# iDProx.net
KiCad netlist of a schematic drawn in Altium Designer
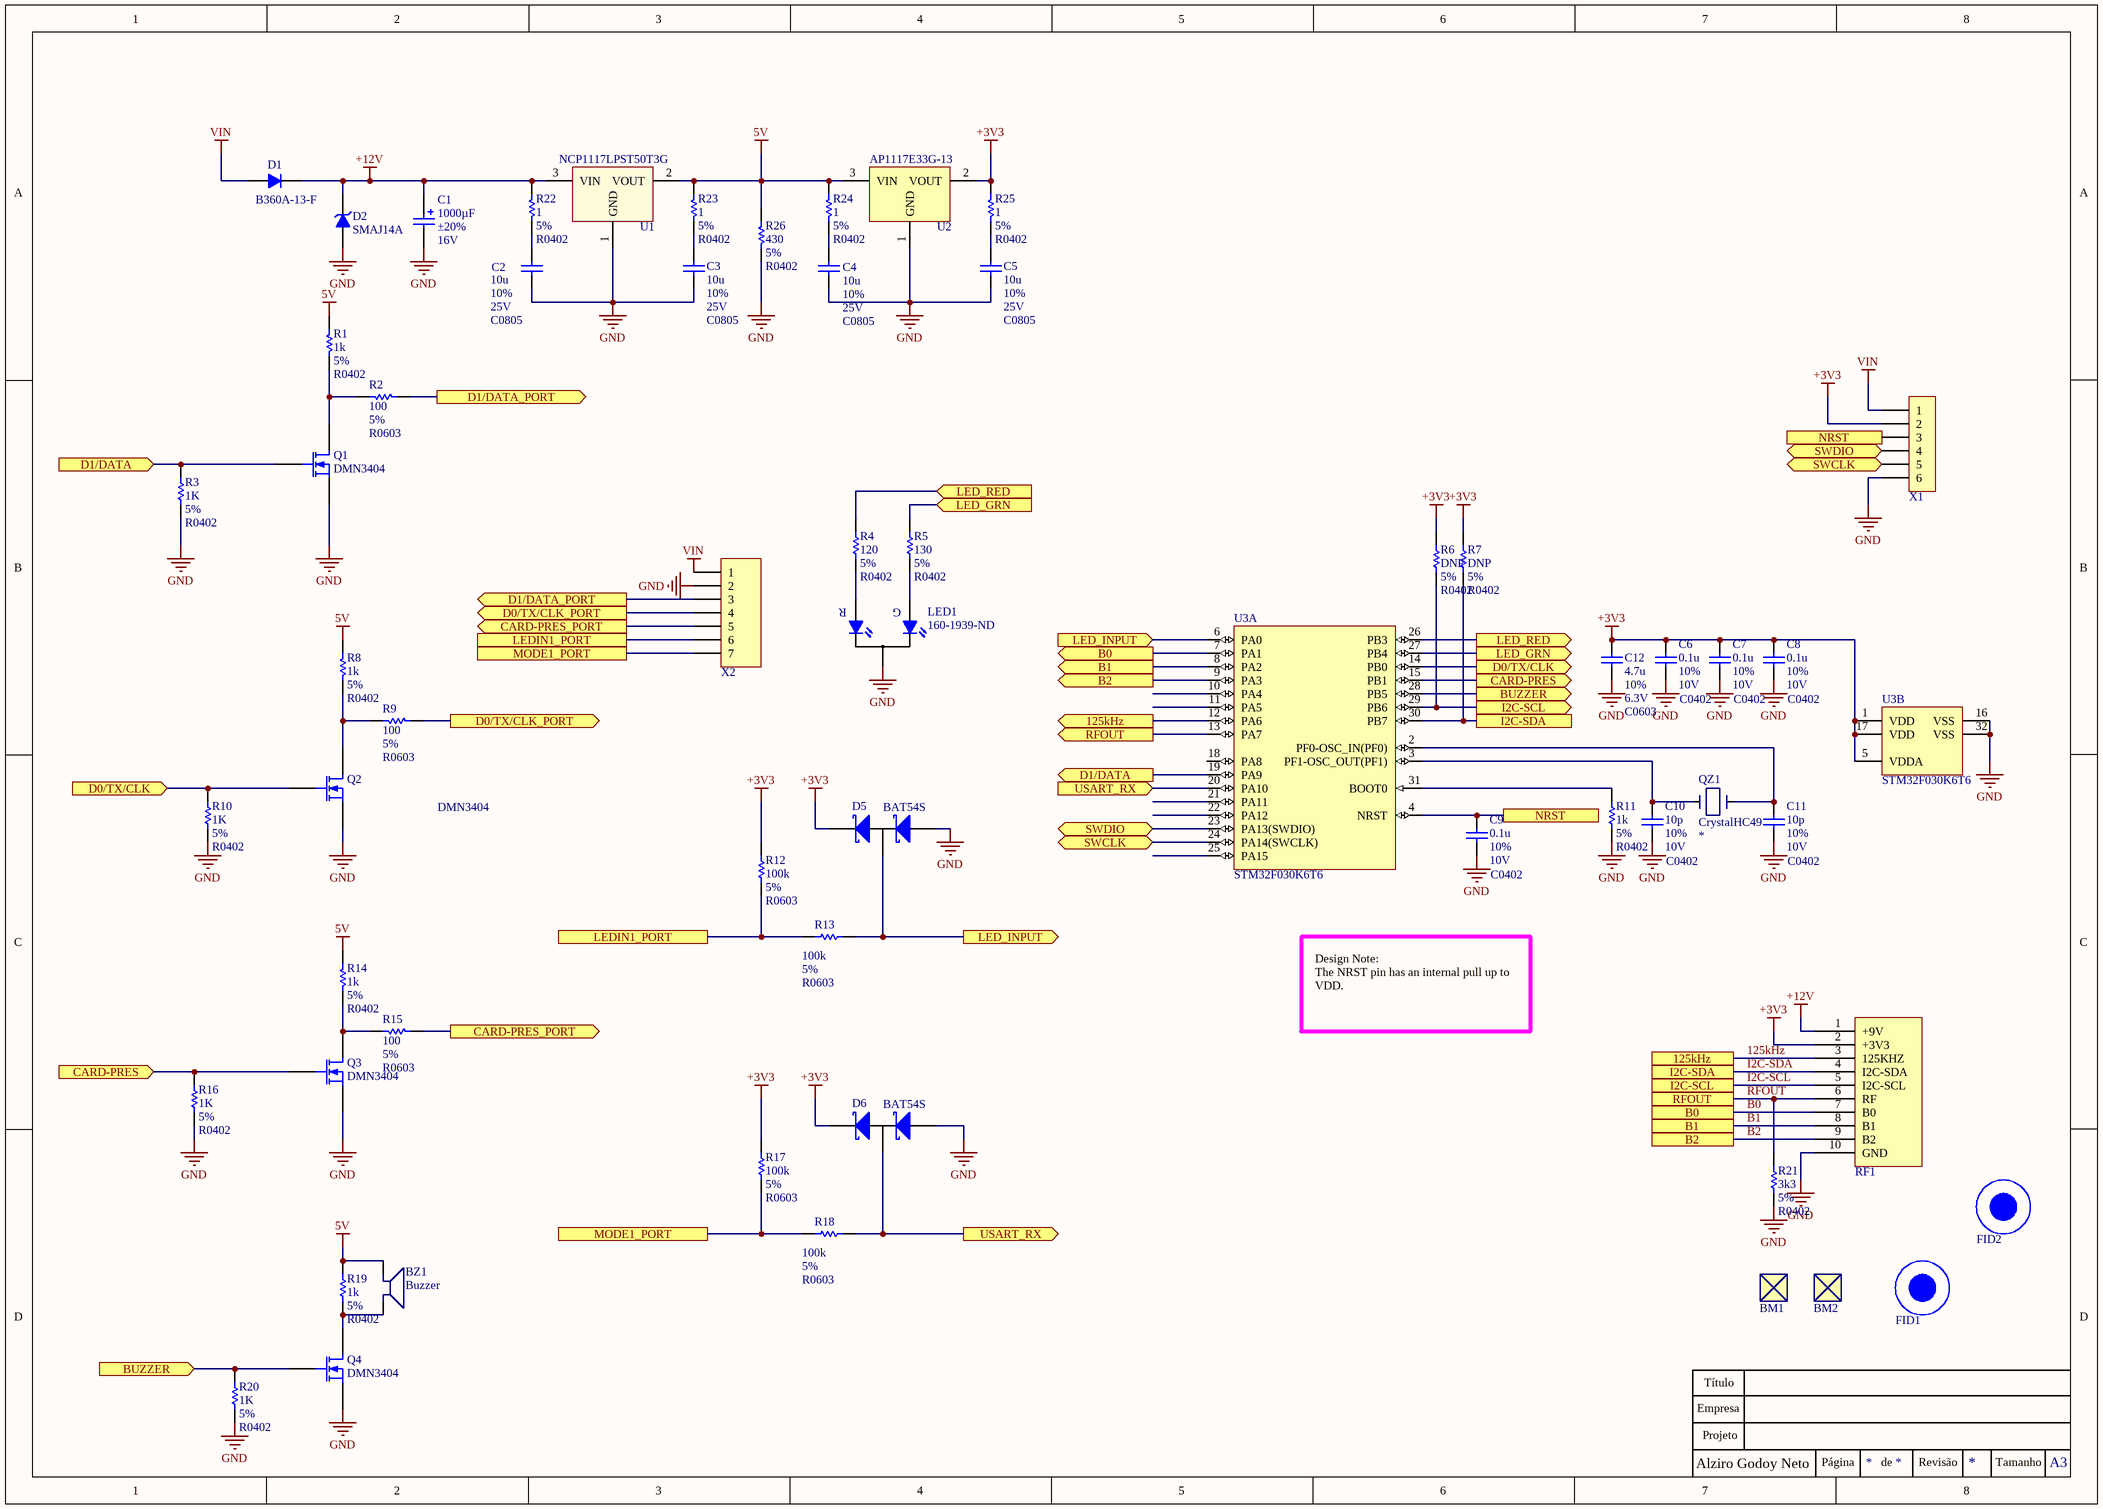
[diagram p0: iDProx.SchDoc]

(export (version "E")
  (design (tool "Eeschema 10.0.6"))
  (components
    (comp (ref "BM1")
      (value "BADMARK")
      (footprint "BADMARK")
      (description "Bad Mark Indicator")
      (libsource (lib "CiDLib") (part "BADMARK"))
    )
    (comp (ref "BM2")
      (value "BADMARK")
      (footprint "BADMARK")
      (description "Bad Mark Indicator")
      (libsource (lib "CiDLib") (part "BADMARK"))
    )
    (comp (ref "BZ1")
      (value "Buzzer")
      (footprint "Buzzer")
      (description "Standard PTH Buzzer")
      (libsource (lib "CiDLib") (part "Buzzer"))
    )
    (comp (ref "C1")
      (value "ESK108M016AH2AA")
      (footprint "ESK108M016AH2AA")
      (description "CAP ALUM 1000UF 20% 16V RADIAL")
      (fields
        (field (name "MANUFACTURER") "Kemet")
        (field (name "CAPACITANCE") "1000µF")
        (field (name "TOLERANCE") "±20%")
        (field (name "VOLTAGE RATING") "16V")
      )
      (libsource (lib "CiDLib") (part "ESK108M016AH2AA"))
    )
    (comp (ref "C2")
      (value "10u")
      (footprint "C0805")
      (description "Capacitor")
      (fields
        (field (name "TOLERANCE") "10%")
        (field (name "MAX VDC") "25V")
        (field (name "Comment") "Cap0805")
      )
      (libsource (lib "CiDLib") (part "Cap0805"))
    )
    (comp (ref "C3")
      (value "10u")
      (footprint "C0805")
      (description "Capacitor")
      (fields
        (field (name "TOLERANCE") "10%")
        (field (name "MAX VDC") "25V")
        (field (name "Comment") "Cap0805")
      )
      (libsource (lib "CiDLib") (part "Cap0805"))
    )
    (comp (ref "C4")
      (value "10u")
      (footprint "C0805")
      (description "Capacitor")
      (fields
        (field (name "TOLERANCE") "10%")
        (field (name "MAX VDC") "25V")
        (field (name "Comment") "Cap0805")
      )
      (libsource (lib "CiDLib") (part "Cap0805"))
    )
    (comp (ref "C5")
      (value "10u")
      (footprint "C0805")
      (description "Capacitor")
      (fields
        (field (name "TOLERANCE") "10%")
        (field (name "MAX VDC") "25V")
        (field (name "Comment") "Cap0805")
      )
      (libsource (lib "CiDLib") (part "Cap0805"))
    )
    (comp (ref "C6")
      (value "0.1u")
      (footprint "C0402")
      (description "Capacitor")
      (fields
        (field (name "TOLERANCE") "10%")
        (field (name "MAX VDC") "10V")
        (field (name "Comment") "Cap0402")
      )
      (libsource (lib "CiDLib") (part "Cap0402"))
    )
    (comp (ref "C7")
      (value "0.1u")
      (footprint "C0402")
      (description "Capacitor")
      (fields
        (field (name "TOLERANCE") "10%")
        (field (name "MAX VDC") "10V")
        (field (name "Comment") "Cap0402")
      )
      (libsource (lib "CiDLib") (part "Cap0402"))
    )
    (comp (ref "C8")
      (value "0.1u")
      (footprint "C0402")
      (description "Capacitor")
      (fields
        (field (name "TOLERANCE") "10%")
        (field (name "MAX VDC") "10V")
        (field (name "Comment") "Cap0402")
      )
      (libsource (lib "CiDLib") (part "Cap0402"))
    )
    (comp (ref "C9")
      (value "0.1u")
      (footprint "C0402")
      (description "Capacitor")
      (fields
        (field (name "TOLERANCE") "10%")
        (field (name "MAX VDC") "10V")
        (field (name "Comment") "Cap0402")
      )
      (libsource (lib "CiDLib") (part "Cap0402"))
    )
    (comp (ref "C10")
      (value "10p")
      (footprint "C0402")
      (description "Capacitor")
      (fields
        (field (name "TOLERANCE") "10%")
        (field (name "MAX VDC") "10V")
        (field (name "Comment") "Cap0402")
      )
      (libsource (lib "CiDLib") (part "Cap0402"))
    )
    (comp (ref "C11")
      (value "10p")
      (footprint "C0402")
      (description "Capacitor")
      (fields
        (field (name "TOLERANCE") "10%")
        (field (name "MAX VDC") "10V")
        (field (name "Comment") "Cap0402")
      )
      (libsource (lib "CiDLib") (part "Cap0402"))
    )
    (comp (ref "C12")
      (value "4.7u")
      (footprint "C0603")
      (description "Capacitor")
      (fields
        (field (name "TOLERANCE") "10%")
        (field (name "MAX VDC") "6.3V")
        (field (name "Comment") "Cap0603")
      )
      (libsource (lib "CiDLib") (part "Cap0603"))
    )
    (comp (ref "D1")
      (value "B360A-13-F")
      (footprint "SMA")
      (description "B360A Diode")
      (fields (field (name "MANUFACTURER") "Diodes Incorporated"))
      (libsource (lib "CiDLib") (part "B360A"))
    )
    (comp (ref "D2")
      (value "SMAJ14A")
      (footprint "SMA")
      (description "TVS DIODE 14VWM 23.2VC SMA")
      (fields (field (name "MANUFACTURER") "Littelfuse Inc."))
      (libsource (lib "CiDLib") (part "SMAJ14A"))
    )
    (comp (ref "D5")
      (value "BAT54S")
      (footprint "SOT23-3")
      (description "DIODE ARRAY SCHOTTKY 30V SOT23")
      (libsource (lib "CiDLib") (part "BAT54S"))
    )
    (comp (ref "D6")
      (value "BAT54S")
      (footprint "SOT23-3")
      (description "DIODE ARRAY SCHOTTKY 30V SOT23")
      (libsource (lib "CiDLib") (part "BAT54S"))
    )
    (comp (ref "FID1")
      (value "FIDUCIAL")
      (footprint "FIDUCIAL-1p5X3")
      (description "Standard fiducial for Control iD boards")
      (libsource (lib "CiDLib") (part "FIDUCIAL"))
    )
    (comp (ref "FID2")
      (value "FIDUCIAL")
      (footprint "FIDUCIAL-1p5X3")
      (description "Standard fiducial for Control iD boards")
      (libsource (lib "CiDLib") (part "FIDUCIAL"))
    )
    (comp (ref "LED1")
      (value "LTL1BEKVJNN")
      (footprint "LTL1BEKVJNN")
      (description "LED GRN/RED DIFF 3MM ROUND T/H")
      (fields
        (field (name "MANUFACTURER") "Lite-On Inc.")
        (field (name "SUPPLIER PART NUMBER 1") "160-1939-ND")
      )
      (libsource (lib "CiDLib") (part "LTL1BEKVJNN"))
    )
    (comp (ref "Q1")
      (value "DMN3404")
      (footprint "SOT23-3")
      (description "DMN3404 N-Channel MOSFET")
      (libsource (lib "CiDLib") (part "DMN3404"))
    )
    (comp (ref "Q2")
      (value "DMN3404")
      (footprint "SOT23-3")
      (description "DMN3404 N-Channel MOSFET")
      (libsource (lib "CiDLib") (part "DMN3404"))
    )
    (comp (ref "Q3")
      (value "DMN3404")
      (footprint "SOT23-3")
      (description "DMN3404 N-Channel MOSFET")
      (libsource (lib "CiDLib") (part "DMN3404"))
    )
    (comp (ref "Q4")
      (value "DMN3404")
      (footprint "SOT23-3")
      (description "DMN3404 N-Channel MOSFET")
      (libsource (lib "CiDLib") (part "DMN3404"))
    )
    (comp (ref "QZ1")
      (value "CrystalHC49")
      (footprint "HC49")
      (fields (field (name "ALTIUM_VALUE") "*"))
      (libsource (lib "CiDLib") (part "CrystalHC49"))
    )
    (comp (ref "R1")
      (value "1k")
      (footprint "R0402")
      (description "Resistor")
      (fields (field (name "TOLERANCE") "5%") (field (name "Comment") "Res0402"))
      (libsource (lib "CiDLib") (part "Res0402"))
    )
    (comp (ref "R2")
      (value "100")
      (footprint "R0603")
      (description "Resistor")
      (fields (field (name "TOLERANCE") "5%") (field (name "Comment") "Res0603"))
      (libsource (lib "CiDLib") (part "Res0603"))
    )
    (comp (ref "R3")
      (value "1K")
      (footprint "R0402")
      (description "Resistor")
      (fields (field (name "TOLERANCE") "5%") (field (name "Comment") "Res0402"))
      (libsource (lib "CiDLib") (part "Res0402"))
    )
    (comp (ref "R4")
      (value "120")
      (footprint "R0402")
      (description "Resistor")
      (fields (field (name "TOLERANCE") "5%") (field (name "Comment") "Res0402"))
      (libsource (lib "CiDLib") (part "Res0402"))
    )
    (comp (ref "R5")
      (value "130")
      (footprint "R0402")
      (description "Resistor")
      (fields (field (name "TOLERANCE") "5%") (field (name "Comment") "Res0402"))
      (libsource (lib "CiDLib") (part "Res0402"))
    )
    (comp (ref "R6")
      (value "DNP")
      (footprint "R0402")
      (description "Resistor")
      (fields (field (name "TOLERANCE") "5%") (field (name "Comment") "Res0402"))
      (libsource (lib "CiDLib") (part "Res0402"))
    )
    (comp (ref "R7")
      (value "DNP")
      (footprint "R0402")
      (description "Resistor")
      (fields (field (name "TOLERANCE") "5%") (field (name "Comment") "Res0402"))
      (libsource (lib "CiDLib") (part "Res0402"))
    )
    (comp (ref "R8")
      (value "1k")
      (footprint "R0402")
      (description "Resistor")
      (fields (field (name "TOLERANCE") "5%") (field (name "Comment") "Res0402"))
      (libsource (lib "CiDLib") (part "Res0402"))
    )
    (comp (ref "R9")
      (value "100")
      (footprint "R0603")
      (description "Resistor")
      (fields (field (name "TOLERANCE") "5%") (field (name "Comment") "Res0603"))
      (libsource (lib "CiDLib") (part "Res0603"))
    )
    (comp (ref "R10")
      (value "1K")
      (footprint "R0402")
      (description "Resistor")
      (fields (field (name "TOLERANCE") "5%") (field (name "Comment") "Res0402"))
      (libsource (lib "CiDLib") (part "Res0402"))
    )
    (comp (ref "R11")
      (value "1k")
      (footprint "R0402")
      (description "Resistor")
      (fields (field (name "TOLERANCE") "5%") (field (name "Comment") "Res0402"))
      (libsource (lib "CiDLib") (part "Res0402"))
    )
    (comp (ref "R12")
      (value "100k")
      (footprint "R0603")
      (description "Resistor")
      (fields (field (name "TOLERANCE") "5%") (field (name "Comment") "Res0603"))
      (libsource (lib "CiDLib") (part "Res0603"))
    )
    (comp (ref "R13")
      (value "100k")
      (footprint "R0603")
      (description "Resistor")
      (fields (field (name "TOLERANCE") "5%") (field (name "Comment") "Res0603"))
      (libsource (lib "CiDLib") (part "Res0603"))
    )
    (comp (ref "R14")
      (value "1k")
      (footprint "R0402")
      (description "Resistor")
      (fields (field (name "TOLERANCE") "5%") (field (name "Comment") "Res0402"))
      (libsource (lib "CiDLib") (part "Res0402"))
    )
    (comp (ref "R15")
      (value "100")
      (footprint "R0603")
      (description "Resistor")
      (fields (field (name "TOLERANCE") "5%") (field (name "Comment") "Res0603"))
      (libsource (lib "CiDLib") (part "Res0603"))
    )
    (comp (ref "R16")
      (value "1K")
      (footprint "R0402")
      (description "Resistor")
      (fields (field (name "TOLERANCE") "5%") (field (name "Comment") "Res0402"))
      (libsource (lib "CiDLib") (part "Res0402"))
    )
    (comp (ref "R17")
      (value "100k")
      (footprint "R0603")
      (description "Resistor")
      (fields (field (name "TOLERANCE") "5%") (field (name "Comment") "Res0603"))
      (libsource (lib "CiDLib") (part "Res0603"))
    )
    (comp (ref "R18")
      (value "100k")
      (footprint "R0603")
      (description "Resistor")
      (fields (field (name "TOLERANCE") "5%") (field (name "Comment") "Res0603"))
      (libsource (lib "CiDLib") (part "Res0603"))
    )
    (comp (ref "R19")
      (value "1k")
      (footprint "R0402")
      (description "Resistor")
      (fields (field (name "TOLERANCE") "5%") (field (name "Comment") "Res0402"))
      (libsource (lib "CiDLib") (part "Res0402"))
    )
    (comp (ref "R20")
      (value "1K")
      (footprint "R0402")
      (description "Resistor")
      (fields (field (name "TOLERANCE") "5%") (field (name "Comment") "Res0402"))
      (libsource (lib "CiDLib") (part "Res0402"))
    )
    (comp (ref "R21")
      (value "3k3")
      (footprint "R0402")
      (description "Resistor")
      (fields (field (name "TOLERANCE") "5%") (field (name "Comment") "Res0402"))
      (libsource (lib "CiDLib") (part "Res0402"))
    )
    (comp (ref "R22")
      (value "1")
      (footprint "R0402")
      (description "Resistor")
      (fields (field (name "TOLERANCE") "5%") (field (name "Comment") "Res0402"))
      (libsource (lib "CiDLib") (part "Res0402"))
    )
    (comp (ref "R23")
      (value "1")
      (footprint "R0402")
      (description "Resistor")
      (fields (field (name "TOLERANCE") "5%") (field (name "Comment") "Res0402"))
      (libsource (lib "CiDLib") (part "Res0402"))
    )
    (comp (ref "R24")
      (value "1")
      (footprint "R0402")
      (description "Resistor")
      (fields (field (name "TOLERANCE") "5%") (field (name "Comment") "Res0402"))
      (libsource (lib "CiDLib") (part "Res0402"))
    )
    (comp (ref "R25")
      (value "1")
      (footprint "R0402")
      (description "Resistor")
      (fields (field (name "TOLERANCE") "5%") (field (name "Comment") "Res0402"))
      (libsource (lib "CiDLib") (part "Res0402"))
    )
    (comp (ref "R26")
      (value "430")
      (footprint "R0402")
      (description "Resistor")
      (fields (field (name "TOLERANCE") "5%") (field (name "Comment") "Res0402"))
      (libsource (lib "CiDLib") (part "Res0402"))
    )
    (comp (ref "RF1")
      (value "REPASK/REPMIF")
      (footprint "REPASK_REPMIF")
      (description "Control iD RF Module")
      (libsource (lib "CiDLib") (part "REPASK/REPMIF"))
    )
    (comp (ref "U1")
      (value "NCP1117LPST50T3G")
      (footprint "SOT223")
      (description "IC REG LDO 5V 1A SOT223")
      (fields (field (name "MANUFACTURER") "ON Semiconductor"))
      (libsource (lib "CiDLib") (part "NCP1117LPST50T3G"))
    )
    (comp (ref "U2")
      (value "AP1117E33G-13")
      (footprint "SOT223")
      (libsource (lib "CiDLib") (part "AP1117E33G-13"))
    )
    (comp (ref "U3")
      (value "STM32F030K6T6")
      (footprint "STM-LQFP32_N")
      (libsource (lib "CiDLib") (part "STM32F030K6T6"))
    )
    (comp (ref "X1")
      (value "Header 6")
      (footprint "1X06")
      (description "Header, 6-Pin, Single row, 0.1\"")
      (libsource (lib "CiDLib") (part "Header 6"))
    )
    (comp (ref "X2")
      (value "JST7_HORIZ")
      (footprint "JST7_HORIZ")
      (libsource (lib "CiDLib") (part "JST7_HORIZ"))
    )
  )
  (nets
    (net (code "1") (name "+3V3") (class "Default")
      (node (ref "C12") (pin "2") (pinfunction "2_2") (pintype "passive"))
      (node (ref "C6") (pin "2") (pinfunction "2_2") (pintype "passive"))
      (node (ref "C7") (pin "2") (pinfunction "2_2") (pintype "passive"))
      (node (ref "C8") (pin "2") (pinfunction "2_2") (pintype "passive"))
      (node (ref "D5") (pin "3") (pinfunction "A1_3") (pintype "passive"))
      (node (ref "D6") (pin "3") (pinfunction "A1_3") (pintype "passive"))
      (node (ref "R12") (pin "2") (pinfunction "2_2") (pintype "passive"))
      (node (ref "R17") (pin "2") (pinfunction "2_2") (pintype "passive"))
      (node (ref "R25") (pin "2") (pinfunction "2_2") (pintype "passive"))
      (node (ref "R6") (pin "2") (pinfunction "2_2") (pintype "passive"))
      (node (ref "R7") (pin "2") (pinfunction "2_2") (pintype "passive"))
      (node (ref "RF1") (pin "2") (pinfunction "+3V3_2") (pintype "passive"))
      (node (ref "U2") (pin "2") (pinfunction "VOUT_2") (pintype "power_in"))
      (node (ref "U3") (pin "1") (pinfunction "VDD_1") (pintype "power_in"))
      (node (ref "U3") (pin "17") (pinfunction "VDD_17") (pintype "power_in"))
      (node (ref "U3") (pin "5") (pinfunction "VDDA_5") (pintype "power_in"))
      (node (ref "X1") (pin "2") (pinfunction "2_2") (pintype "passive"))
    )
    (net (code "2") (name "+12V") (class "Default")
      (node (ref "C1") (pin "1") (pinfunction "1_1") (pintype "passive"))
      (node (ref "D1") (pin "2") (pinfunction "K_2") (pintype "passive"))
      (node (ref "D2") (pin "2") (pinfunction "K_2") (pintype "passive"))
      (node (ref "R22") (pin "2") (pinfunction "2_2") (pintype "passive"))
      (node (ref "RF1") (pin "1") (pinfunction "+9V_1") (pintype "passive"))
      (node (ref "U1") (pin "3") (pinfunction "VIN_3") (pintype "power_in"))
    )
    (net (code "3") (name "/125kHz") (class "Default")
      (node (ref "RF1") (pin "3") (pinfunction "125KHZ_3") (pintype "passive"))
      (node (ref "U3") (pin "12") (pinfunction "PA6_12") (pintype "bidirectional"))
    )
    (net (code "4") (name "/B0") (class "Default")
      (node (ref "RF1") (pin "7") (pinfunction "B0_7") (pintype "passive"))
      (node (ref "U3") (pin "7") (pinfunction "PA1_7") (pintype "bidirectional"))
    )
    (net (code "5") (name "/B1") (class "Default")
      (node (ref "RF1") (pin "8") (pinfunction "B1_8") (pintype "passive"))
      (node (ref "U3") (pin "8") (pinfunction "PA2_8") (pintype "bidirectional"))
    )
    (net (code "6") (name "/B2") (class "Default")
      (node (ref "RF1") (pin "9") (pinfunction "B2_9") (pintype "passive"))
      (node (ref "U3") (pin "9") (pinfunction "PA3_9") (pintype "bidirectional"))
    )
    (net (code "7") (name "/BUZZER") (class "Default")
      (node (ref "Q4") (pin "2") (pinfunction "G_2") (pintype "passive"))
      (node (ref "R20") (pin "2") (pinfunction "2_2") (pintype "passive"))
      (node (ref "U3") (pin "28") (pinfunction "PB5_28") (pintype "bidirectional"))
    )
    (net (code "8") (name "/CARD-PRES") (class "Default")
      (node (ref "Q3") (pin "2") (pinfunction "G_2") (pintype "passive"))
      (node (ref "R16") (pin "2") (pinfunction "2_2") (pintype "passive"))
      (node (ref "U3") (pin "15") (pinfunction "PB1_15") (pintype "bidirectional"))
    )
    (net (code "9") (name "/CARD-PRES_PORT") (class "Default")
      (node (ref "R15") (pin "1") (pinfunction "1_1") (pintype "passive"))
      (node (ref "X2") (pin "5") (pinfunction "5_5") (pintype "passive"))
    )
    (net (code "10") (name "/D0{slash}TX{slash}CLK") (class "Default")
      (node (ref "Q2") (pin "2") (pinfunction "G_2") (pintype "passive"))
      (node (ref "R10") (pin "2") (pinfunction "2_2") (pintype "passive"))
      (node (ref "U3") (pin "14") (pinfunction "PB0_14") (pintype "bidirectional"))
    )
    (net (code "11") (name "/D0{slash}TX{slash}CLK_PORT") (class "Default")
      (node (ref "R9") (pin "1") (pinfunction "1_1") (pintype "passive"))
      (node (ref "X2") (pin "4") (pinfunction "4_4") (pintype "passive"))
    )
    (net (code "12") (name "/D1{slash}DATA") (class "Default")
      (node (ref "Q1") (pin "2") (pinfunction "G_2") (pintype "passive"))
      (node (ref "R3") (pin "2") (pinfunction "2_2") (pintype "passive"))
      (node (ref "U3") (pin "19") (pinfunction "PA9_19") (pintype "bidirectional"))
    )
    (net (code "13") (name "/D1{slash}DATA_PORT") (class "Default")
      (node (ref "R2") (pin "1") (pinfunction "1_1") (pintype "passive"))
      (node (ref "X2") (pin "3") (pinfunction "3_3") (pintype "passive"))
    )
    (net (code "14") (name "/I2C-SCL") (class "Default")
      (node (ref "R6") (pin "1") (pinfunction "1_1") (pintype "passive"))
      (node (ref "RF1") (pin "5") (pinfunction "I2C-SCL_5") (pintype "passive"))
      (node (ref "U3") (pin "29") (pinfunction "PB6_29") (pintype "bidirectional"))
    )
    (net (code "15") (name "/I2C-SDA") (class "Default")
      (node (ref "R7") (pin "1") (pinfunction "1_1") (pintype "passive"))
      (node (ref "RF1") (pin "4") (pinfunction "I2C-SDA_4") (pintype "passive"))
      (node (ref "U3") (pin "30") (pinfunction "PB7_30") (pintype "bidirectional"))
    )
    (net (code "16") (name "/LEDIN1_PORT") (class "Default")
      (node (ref "R12") (pin "1") (pinfunction "1_1") (pintype "passive"))
      (node (ref "R13") (pin "1") (pinfunction "1_1") (pintype "passive"))
      (node (ref "X2") (pin "6") (pinfunction "6_6") (pintype "passive"))
    )
    (net (code "17") (name "/LED_GRN") (class "Default")
      (node (ref "R5") (pin "2") (pinfunction "2_2") (pintype "passive"))
      (node (ref "U3") (pin "27") (pinfunction "PB4_27") (pintype "bidirectional"))
    )
    (net (code "18") (name "/LED_INPUT") (class "Default")
      (node (ref "D5") (pin "1") (pinfunction "K_1") (pintype "passive"))
      (node (ref "R13") (pin "2") (pinfunction "2_2") (pintype "passive"))
      (node (ref "U3") (pin "6") (pinfunction "PA0_6") (pintype "bidirectional"))
    )
    (net (code "19") (name "/LED_RED") (class "Default")
      (node (ref "R4") (pin "2") (pinfunction "2_2") (pintype "passive"))
      (node (ref "U3") (pin "26") (pinfunction "PB3_26") (pintype "bidirectional"))
    )
    (net (code "20") (name "/MODE1_PORT") (class "Default")
      (node (ref "R17") (pin "1") (pinfunction "1_1") (pintype "passive"))
      (node (ref "R18") (pin "1") (pinfunction "1_1") (pintype "passive"))
      (node (ref "X2") (pin "7") (pinfunction "7_7") (pintype "passive"))
    )
    (net (code "21") (name "/NRST") (class "Default")
      (node (ref "C9") (pin "2") (pinfunction "2_2") (pintype "passive"))
      (node (ref "U3") (pin "4") (pinfunction "NRST_4") (pintype "bidirectional"))
      (node (ref "X1") (pin "3") (pinfunction "3_3") (pintype "passive"))
    )
    (net (code "22") (name "/RFOUT") (class "Default")
      (node (ref "R21") (pin "2") (pinfunction "2_2") (pintype "passive"))
      (node (ref "RF1") (pin "6") (pinfunction "RF_6") (pintype "passive"))
      (node (ref "U3") (pin "13") (pinfunction "PA7_13") (pintype "bidirectional"))
    )
    (net (code "23") (name "/SWCLK") (class "Default")
      (node (ref "U3") (pin "24") (pinfunction "PA14(SWCLK)_24") (pintype "bidirectional"))
      (node (ref "X1") (pin "5") (pinfunction "5_5") (pintype "passive"))
    )
    (net (code "24") (name "/SWDIO") (class "Default")
      (node (ref "U3") (pin "23") (pinfunction "PA13(SWDIO)_23") (pintype "bidirectional"))
      (node (ref "X1") (pin "4") (pinfunction "4_4") (pintype "passive"))
    )
    (net (code "25") (name "/USART_RX") (class "Default")
      (node (ref "D6") (pin "1") (pinfunction "K_1") (pintype "passive"))
      (node (ref "R18") (pin "2") (pinfunction "2_2") (pintype "passive"))
      (node (ref "U3") (pin "20") (pinfunction "PA10_20") (pintype "bidirectional"))
    )
    (net (code "26") (name "5V") (class "Default")
      (node (ref "BZ1") (pin "1") (pinfunction "1_1") (pintype "passive"))
      (node (ref "R1") (pin "2") (pinfunction "2_2") (pintype "passive"))
      (node (ref "R14") (pin "2") (pinfunction "2_2") (pintype "passive"))
      (node (ref "R19") (pin "2") (pinfunction "2_2") (pintype "passive"))
      (node (ref "R23") (pin "2") (pinfunction "2_2") (pintype "passive"))
      (node (ref "R24") (pin "2") (pinfunction "2_2") (pintype "passive"))
      (node (ref "R26") (pin "2") (pinfunction "2_2") (pintype "passive"))
      (node (ref "R8") (pin "2") (pinfunction "2_2") (pintype "passive"))
      (node (ref "U1") (pin "2") (pinfunction "VOUT_2") (pintype "power_in"))
      (node (ref "U2") (pin "3") (pinfunction "VIN_3") (pintype "power_in"))
    )
    (net (code "27") (name "GND") (class "Default")
      (node (ref "C1") (pin "2") (pinfunction "2_2") (pintype "passive"))
      (node (ref "C10") (pin "1") (pinfunction "1_1") (pintype "passive"))
      (node (ref "C11") (pin "1") (pinfunction "1_1") (pintype "passive"))
      (node (ref "C12") (pin "1") (pinfunction "1_1") (pintype "passive"))
      (node (ref "C2") (pin "2") (pinfunction "2_2") (pintype "passive"))
      (node (ref "C3") (pin "1") (pinfunction "1_1") (pintype "passive"))
      (node (ref "C4") (pin "2") (pinfunction "2_2") (pintype "passive"))
      (node (ref "C5") (pin "1") (pinfunction "1_1") (pintype "passive"))
      (node (ref "C6") (pin "1") (pinfunction "1_1") (pintype "passive"))
      (node (ref "C7") (pin "1") (pinfunction "1_1") (pintype "passive"))
      (node (ref "C8") (pin "1") (pinfunction "1_1") (pintype "passive"))
      (node (ref "C9") (pin "1") (pinfunction "1_1") (pintype "passive"))
      (node (ref "D2") (pin "1") (pinfunction "A_1") (pintype "passive"))
      (node (ref "D5") (pin "2") (pinfunction "A2_2") (pintype "passive"))
      (node (ref "D6") (pin "2") (pinfunction "A2_2") (pintype "passive"))
      (node (ref "LED1") (pin "2") (pinfunction "K_2") (pintype "passive"))
      (node (ref "Q1") (pin "3") (pinfunction "S_3") (pintype "passive"))
      (node (ref "Q2") (pin "3") (pinfunction "S_3") (pintype "passive"))
      (node (ref "Q3") (pin "3") (pinfunction "S_3") (pintype "passive"))
      (node (ref "Q4") (pin "3") (pinfunction "S_3") (pintype "passive"))
      (node (ref "R10") (pin "1") (pinfunction "1_1") (pintype "passive"))
      (node (ref "R11") (pin "1") (pinfunction "1_1") (pintype "passive"))
      (node (ref "R16") (pin "1") (pinfunction "1_1") (pintype "passive"))
      (node (ref "R20") (pin "1") (pinfunction "1_1") (pintype "passive"))
      (node (ref "R21") (pin "1") (pinfunction "1_1") (pintype "passive"))
      (node (ref "R26") (pin "1") (pinfunction "1_1") (pintype "passive"))
      (node (ref "R3") (pin "1") (pinfunction "1_1") (pintype "passive"))
      (node (ref "RF1") (pin "10") (pinfunction "GND_10") (pintype "passive"))
      (node (ref "U1") (pin "1") (pinfunction "GND_1") (pintype "power_in"))
      (node (ref "U2") (pin "1") (pinfunction "GND_1") (pintype "power_in"))
      (node (ref "U3") (pin "16") (pinfunction "VSS_16") (pintype "power_in"))
      (node (ref "U3") (pin "32") (pinfunction "VSS_32") (pintype "power_in"))
      (node (ref "X1") (pin "6") (pinfunction "6_6") (pintype "passive"))
      (node (ref "X2") (pin "2") (pinfunction "2_2") (pintype "passive"))
    )
    (net (code "28") (name "Net-(C2-Pad1)") (class "Default")
      (node (ref "C2") (pin "1") (pinfunction "1_1") (pintype "passive"))
      (node (ref "R22") (pin "1") (pinfunction "1_1") (pintype "passive"))
    )
    (net (code "29") (name "Net-(C3-Pad2)") (class "Default")
      (node (ref "C3") (pin "2") (pinfunction "2_2") (pintype "passive"))
      (node (ref "R23") (pin "1") (pinfunction "1_1") (pintype "passive"))
    )
    (net (code "30") (name "Net-(C4-Pad1)") (class "Default")
      (node (ref "C4") (pin "1") (pinfunction "1_1") (pintype "passive"))
      (node (ref "R24") (pin "1") (pinfunction "1_1") (pintype "passive"))
    )
    (net (code "31") (name "Net-(C5-Pad2)") (class "Default")
      (node (ref "C5") (pin "2") (pinfunction "2_2") (pintype "passive"))
      (node (ref "R25") (pin "1") (pinfunction "1_1") (pintype "passive"))
    )
    (net (code "32") (name "Net-(LED1-AG)") (class "Default")
      (node (ref "LED1") (pin "3") (pinfunction "AG_3") (pintype "passive"))
      (node (ref "R5") (pin "1") (pinfunction "1_1") (pintype "passive"))
    )
    (net (code "33") (name "Net-(LED1-AR)") (class "Default")
      (node (ref "LED1") (pin "1") (pinfunction "AR_1") (pintype "passive"))
      (node (ref "R4") (pin "1") (pinfunction "1_1") (pintype "passive"))
    )
    (net (code "34") (name "Net-(Q1-D)") (class "Default")
      (node (ref "Q1") (pin "1") (pinfunction "D_1") (pintype "passive"))
      (node (ref "R1") (pin "1") (pinfunction "1_1") (pintype "passive"))
      (node (ref "R2") (pin "2") (pinfunction "2_2") (pintype "passive"))
    )
    (net (code "35") (name "Net-(Q2-D)") (class "Default")
      (node (ref "Q2") (pin "1") (pinfunction "D_1") (pintype "passive"))
      (node (ref "R8") (pin "1") (pinfunction "1_1") (pintype "passive"))
      (node (ref "R9") (pin "2") (pinfunction "2_2") (pintype "passive"))
    )
    (net (code "36") (name "Net-(Q3-D)") (class "Default")
      (node (ref "Q3") (pin "1") (pinfunction "D_1") (pintype "passive"))
      (node (ref "R14") (pin "1") (pinfunction "1_1") (pintype "passive"))
      (node (ref "R15") (pin "2") (pinfunction "2_2") (pintype "passive"))
    )
    (net (code "37") (name "Net-(Q4-D)") (class "Default")
      (node (ref "BZ1") (pin "2") (pinfunction "2_2") (pintype "passive"))
      (node (ref "Q4") (pin "1") (pinfunction "D_1") (pintype "passive"))
      (node (ref "R19") (pin "1") (pinfunction "1_1") (pintype "passive"))
    )
    (net (code "38") (name "Net-(QZ1-X1)") (class "Default")
      (node (ref "C11") (pin "2") (pinfunction "2_2") (pintype "passive"))
      (node (ref "QZ1") (pin "1") (pinfunction "X1_1") (pintype "passive"))
      (node (ref "U3") (pin "2") (pinfunction "PF0-OSC_IN(PF0)_2") (pintype "bidirectional"))
    )
    (net (code "39") (name "Net-(QZ1-X2)") (class "Default")
      (node (ref "C10") (pin "2") (pinfunction "2_2") (pintype "passive"))
      (node (ref "QZ1") (pin "2") (pinfunction "X2_2") (pintype "passive"))
      (node (ref "U3") (pin "3") (pinfunction "PF1-OSC_OUT(PF1)_3") (pintype "bidirectional"))
    )
    (net (code "40") (name "Net-(U3A-BOOT0)") (class "Default")
      (node (ref "R11") (pin "2") (pinfunction "2_2") (pintype "passive"))
      (node (ref "U3") (pin "31") (pinfunction "BOOT0_31") (pintype "input"))
    )
    (net (code "41") (name "VIN") (class "Default")
      (node (ref "D1") (pin "1") (pinfunction "A_1") (pintype "passive"))
      (node (ref "X1") (pin "1") (pinfunction "1_1") (pintype "passive"))
      (node (ref "X2") (pin "1") (pinfunction "1_1") (pintype "passive"))
    )
    (net (code "42") (name "unconnected-(U3A-PA4-Pad10)") (class "Default")
      (node (ref "U3") (pin "10") (pinfunction "PA4_10") (pintype "bidirectional"))
    )
    (net (code "43") (name "unconnected-(U3A-PA5-Pad11)") (class "Default")
      (node (ref "U3") (pin "11") (pinfunction "PA5_11") (pintype "bidirectional"))
    )
    (net (code "44") (name "unconnected-(U3A-PA8-Pad18)") (class "Default")
      (node (ref "U3") (pin "18") (pinfunction "PA8_18") (pintype "bidirectional"))
    )
    (net (code "45") (name "unconnected-(U3A-PA11-Pad21)") (class "Default")
      (node (ref "U3") (pin "21") (pinfunction "PA11_21") (pintype "bidirectional"))
    )
    (net (code "46") (name "unconnected-(U3A-PA12-Pad22)") (class "Default")
      (node (ref "U3") (pin "22") (pinfunction "PA12_22") (pintype "bidirectional"))
    )
    (net (code "47") (name "unconnected-(U3A-PA15-Pad25)") (class "Default")
      (node (ref "U3") (pin "25") (pinfunction "PA15_25") (pintype "bidirectional"))
    )
  )
)
